# Switching_Regulator_LV.net
KiCad netlist of a schematic drawn in Altium Designer
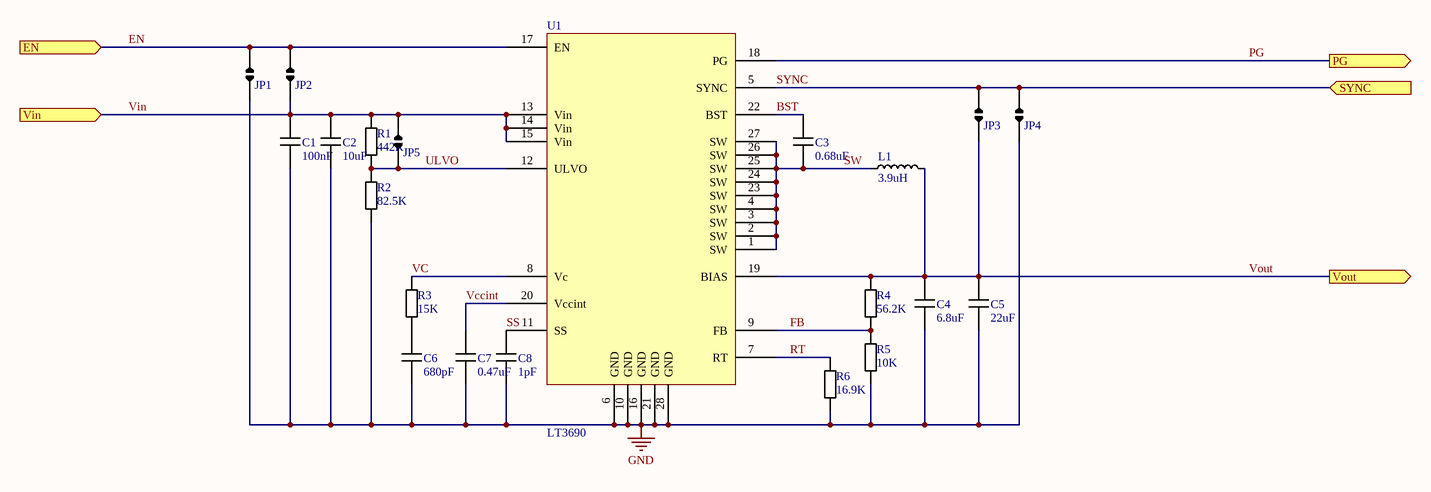
[diagram p0: Switching_Regulator_LV.SchDoc]

(export (version "E")
  (design (tool "Eeschema 10.0.6"))
  (components
    (comp (ref "C1")
      (value "100nF")
      (footprint "0805 Cap")
      (description "0805 MLCC - X7R, 10%")
      (fields (field (name "Comment") "0805 Cap"))
      (libsource (lib "Schlib1") (part "0805 MLCC - X7R, 10%"))
    )
    (comp (ref "C2")
      (value "10uF")
      (footprint "1206 Cap")
      (description "1206 MLCC - X7R, 10%")
      (fields (field (name "Comment") "1206 Cap"))
      (libsource (lib "Schlib1") (part "1206 MLCC - X7R, 10%"))
    )
    (comp (ref "C3")
      (value "0.68uF")
      (footprint "0805 Cap")
      (description "0805 MLCC - X7R, 10%")
      (fields (field (name "Comment") "0805 Cap"))
      (libsource (lib "Schlib1") (part "0805 MLCC - X7R, 10%"))
    )
    (comp (ref "C4")
      (value "6.8uF")
      (footprint "0805 Cap")
      (description "0805 MLCC - X7R, 10%")
      (fields (field (name "Comment") "0805 Cap"))
      (libsource (lib "Schlib1") (part "0805 MLCC - X7R, 10%"))
    )
    (comp (ref "C5")
      (value "22uF")
      (footprint "1206 Cap")
      (description "1206 MLCC - X7R, 10%")
      (fields (field (name "Comment") "1206 Cap"))
      (libsource (lib "Schlib1") (part "1206 MLCC - X7R, 10%"))
    )
    (comp (ref "C6")
      (value "680pF")
      (footprint "0805 Cap")
      (description "0805 MLCC - NP0, 5%")
      (fields (field (name "Comment") "0805 Cap"))
      (libsource (lib "Schlib1") (part "0805 MLCC - NP0, 5%"))
    )
    (comp (ref "C7")
      (value "0.47uF")
      (footprint "0805 Cap")
      (description "0805 MLCC - X7R, 10%")
      (fields (field (name "Comment") "0805 Cap"))
      (libsource (lib "Schlib1") (part "0805 MLCC - X7R, 10%"))
    )
    (comp (ref "C8")
      (value "1pF")
      (footprint "0805 Cap")
      (description "0805 MLCC - NP0, 5%")
      (fields (field (name "Comment") "0805 Cap"))
      (libsource (lib "Schlib1") (part "0805 MLCC - NP0, 5%"))
    )
    (comp (ref "JP1")
      (value "Jumper")
      (footprint "Solder Jumper C")
      (description "Solder Bridge")
      (libsource (lib "Schlib1") (part "Solder Bridge"))
    )
    (comp (ref "JP2")
      (value "Jumper")
      (footprint "Solder Jumper C")
      (description "Solder Bridge")
      (libsource (lib "Schlib1") (part "Solder Bridge"))
    )
    (comp (ref "JP3")
      (value "Jumper")
      (footprint "Solder Jumper C")
      (description "Solder Bridge")
      (libsource (lib "Schlib1") (part "Solder Bridge"))
    )
    (comp (ref "JP4")
      (value "Jumper")
      (footprint "Solder Jumper C")
      (description "Solder Bridge")
      (libsource (lib "Schlib1") (part "Solder Bridge"))
    )
    (comp (ref "JP5")
      (value "Jumper")
      (footprint "Solder Jumper C")
      (description "Solder Bridge")
      (libsource (lib "Schlib1") (part "Solder Bridge"))
    )
    (comp (ref "L1")
      (value "3.9uH")
      (footprint "INDP4037X16N")
      (description "Inductor 4x4mm 2.2uH")
      (fields (field (name "Comment") "LQH44PN2R2MP0"))
      (libsource (lib "Schlib1") (part "LQH44PN2R2MP0"))
    )
    (comp (ref "R1")
      (value "442K")
      (footprint "0805 Resistor")
      (description "0805 Thick Film Resistor 1%")
      (fields (field (name "Comment") "0805 Resistor"))
      (libsource (lib "Schlib1") (part "0805 Thick Film Resistor 1%"))
    )
    (comp (ref "R2")
      (value "82.5K")
      (footprint "0805 Resistor")
      (description "0805 Thick Film Resistor 1%")
      (fields (field (name "Comment") "0805 Resistor"))
      (libsource (lib "Schlib1") (part "0805 Thick Film Resistor 1%"))
    )
    (comp (ref "R3")
      (value "15K")
      (footprint "0805 Resistor")
      (description "0805 Thick Film Resistor 1%")
      (fields (field (name "Comment") "0805 Resistor"))
      (libsource (lib "Schlib1") (part "0805 Thick Film Resistor 1%"))
    )
    (comp (ref "R4")
      (value "56.2K")
      (footprint "0805 Resistor")
      (description "0805 Thick Film Resistor 1%")
      (fields (field (name "Comment") "0805 Resistor"))
      (libsource (lib "Schlib1") (part "0805 Thick Film Resistor 1%"))
    )
    (comp (ref "R5")
      (value "10K")
      (footprint "0805 Resistor")
      (description "0805 Thick Film Resistor 1%")
      (fields (field (name "Comment") "0805 Resistor"))
      (libsource (lib "Schlib1") (part "0805 Thick Film Resistor 1%"))
    )
    (comp (ref "R6")
      (value "16.9K")
      (footprint "0805 Resistor")
      (description "0805 Thick Film Resistor 1%")
      (fields (field (name "Comment") "0805 Resistor"))
      (libsource (lib "Schlib1") (part "0805 Thick Film Resistor 1%"))
    )
    (comp (ref "U1") (value "LT3690") (footprint "LT3690") (libsource (lib "Schlib1") (part "LT3690")))
  )
  (nets
    (net (code "1") (name "/BST") (class "Default")
      (node (ref "C3") (pin "2") (pinfunction "2_2") (pintype "passive"))
      (node (ref "U1") (pin "22") (pinfunction "BST_22") (pintype "passive"))
    )
    (net (code "2") (name "/EN") (class "Default")
      (node (ref "JP1") (pin "1") (pinfunction "1_1") (pintype "passive"))
      (node (ref "JP2") (pin "1") (pinfunction "1_1") (pintype "passive"))
      (node (ref "U1") (pin "17") (pinfunction "EN_17") (pintype "passive"))
    )
    (net (code "3") (name "/FB") (class "Default")
      (node (ref "R4") (pin "1") (pinfunction "1_1") (pintype "passive"))
      (node (ref "R5") (pin "2") (pinfunction "2_2") (pintype "passive"))
      (node (ref "U1") (pin "9") (pinfunction "FB_9") (pintype "passive"))
    )
    (net (code "4") (name "/PG") (class "Default")
      (node (ref "U1") (pin "18") (pinfunction "PG_18") (pintype "passive"))
    )
    (net (code "5") (name "/RT") (class "Default")
      (node (ref "R6") (pin "2") (pinfunction "2_2") (pintype "passive"))
      (node (ref "U1") (pin "7") (pinfunction "RT_7") (pintype "passive"))
    )
    (net (code "6") (name "/SS") (class "Default")
      (node (ref "C8") (pin "2") (pinfunction "2_2") (pintype "passive"))
      (node (ref "U1") (pin "11") (pinfunction "SS_11") (pintype "passive"))
    )
    (net (code "7") (name "/SW") (class "Default")
      (node (ref "C3") (pin "1") (pinfunction "1_1") (pintype "passive"))
      (node (ref "L1") (pin "1") (pinfunction "1_1") (pintype "passive"))
      (node (ref "U1") (pin "1") (pinfunction "SW_1") (pintype "passive"))
      (node (ref "U1") (pin "2") (pinfunction "SW_2") (pintype "passive"))
      (node (ref "U1") (pin "23") (pinfunction "SW_23") (pintype "passive"))
      (node (ref "U1") (pin "24") (pinfunction "SW_24") (pintype "passive"))
      (node (ref "U1") (pin "25") (pinfunction "SW_25") (pintype "passive"))
      (node (ref "U1") (pin "26") (pinfunction "SW_26") (pintype "passive"))
      (node (ref "U1") (pin "27") (pinfunction "SW_27") (pintype "passive"))
      (node (ref "U1") (pin "3") (pinfunction "SW_3") (pintype "passive"))
      (node (ref "U1") (pin "4") (pinfunction "SW_4") (pintype "passive"))
    )
    (net (code "8") (name "/SYNC") (class "Default")
      (node (ref "JP3") (pin "1") (pinfunction "1_1") (pintype "passive"))
      (node (ref "JP4") (pin "1") (pinfunction "1_1") (pintype "passive"))
      (node (ref "U1") (pin "5") (pinfunction "SYNC_5") (pintype "passive"))
    )
    (net (code "9") (name "/ULVO") (class "Default")
      (node (ref "JP5") (pin "2") (pinfunction "2_2") (pintype "passive"))
      (node (ref "R1") (pin "1") (pinfunction "1_1") (pintype "passive"))
      (node (ref "R2") (pin "2") (pinfunction "2_2") (pintype "passive"))
      (node (ref "U1") (pin "12") (pinfunction "ULVO_12") (pintype "passive"))
    )
    (net (code "10") (name "/VC") (class "Default")
      (node (ref "R3") (pin "2") (pinfunction "2_2") (pintype "passive"))
      (node (ref "U1") (pin "8") (pinfunction "Vc_8") (pintype "passive"))
    )
    (net (code "11") (name "/Vccint") (class "Default")
      (node (ref "C7") (pin "2") (pinfunction "2_2") (pintype "passive"))
      (node (ref "U1") (pin "20") (pinfunction "Vccint_20") (pintype "passive"))
    )
    (net (code "12") (name "/Vin") (class "Default")
      (node (ref "C1") (pin "2") (pinfunction "2_2") (pintype "passive"))
      (node (ref "C2") (pin "2") (pinfunction "2_2") (pintype "passive"))
      (node (ref "JP2") (pin "2") (pinfunction "2_2") (pintype "passive"))
      (node (ref "JP5") (pin "1") (pinfunction "1_1") (pintype "passive"))
      (node (ref "R1") (pin "2") (pinfunction "2_2") (pintype "passive"))
      (node (ref "U1") (pin "13") (pinfunction "Vin_13") (pintype "passive"))
      (node (ref "U1") (pin "14") (pinfunction "Vin_14") (pintype "passive"))
      (node (ref "U1") (pin "15") (pinfunction "Vin_15") (pintype "passive"))
    )
    (net (code "13") (name "/Vout") (class "Default")
      (node (ref "C4") (pin "2") (pinfunction "2_2") (pintype "passive"))
      (node (ref "C5") (pin "2") (pinfunction "2_2") (pintype "passive"))
      (node (ref "JP3") (pin "2") (pinfunction "2_2") (pintype "passive"))
      (node (ref "L1") (pin "2") (pinfunction "2_2") (pintype "passive"))
      (node (ref "R4") (pin "2") (pinfunction "2_2") (pintype "passive"))
      (node (ref "U1") (pin "19") (pinfunction "BIAS_19") (pintype "passive"))
    )
    (net (code "14") (name "GND") (class "Default")
      (node (ref "C1") (pin "1") (pinfunction "1_1") (pintype "passive"))
      (node (ref "C2") (pin "1") (pinfunction "1_1") (pintype "passive"))
      (node (ref "C4") (pin "1") (pinfunction "1_1") (pintype "passive"))
      (node (ref "C5") (pin "1") (pinfunction "1_1") (pintype "passive"))
      (node (ref "C6") (pin "1") (pinfunction "1_1") (pintype "passive"))
      (node (ref "C7") (pin "1") (pinfunction "1_1") (pintype "passive"))
      (node (ref "C8") (pin "1") (pinfunction "1_1") (pintype "passive"))
      (node (ref "JP1") (pin "2") (pinfunction "2_2") (pintype "passive"))
      (node (ref "JP4") (pin "2") (pinfunction "2_2") (pintype "passive"))
      (node (ref "R2") (pin "1") (pinfunction "1_1") (pintype "passive"))
      (node (ref "R5") (pin "1") (pinfunction "1_1") (pintype "passive"))
      (node (ref "R6") (pin "1") (pinfunction "1_1") (pintype "passive"))
      (node (ref "U1") (pin "10") (pinfunction "GND_10") (pintype "passive"))
      (node (ref "U1") (pin "16") (pinfunction "GND_16") (pintype "passive"))
      (node (ref "U1") (pin "21") (pinfunction "GND_21") (pintype "passive"))
      (node (ref "U1") (pin "28") (pinfunction "GND_28") (pintype "passive"))
      (node (ref "U1") (pin "6") (pinfunction "GND_6") (pintype "passive"))
    )
    (net (code "15") (name "Net-(C6-Pad2)") (class "Default")
      (node (ref "C6") (pin "2") (pinfunction "2_2") (pintype "passive"))
      (node (ref "R3") (pin "1") (pinfunction "1_1") (pintype "passive"))
    )
  )
)
